# Kickliter_Trevor_Lab_9.net
KiCad netlist of a schematic drawn in EAGLE
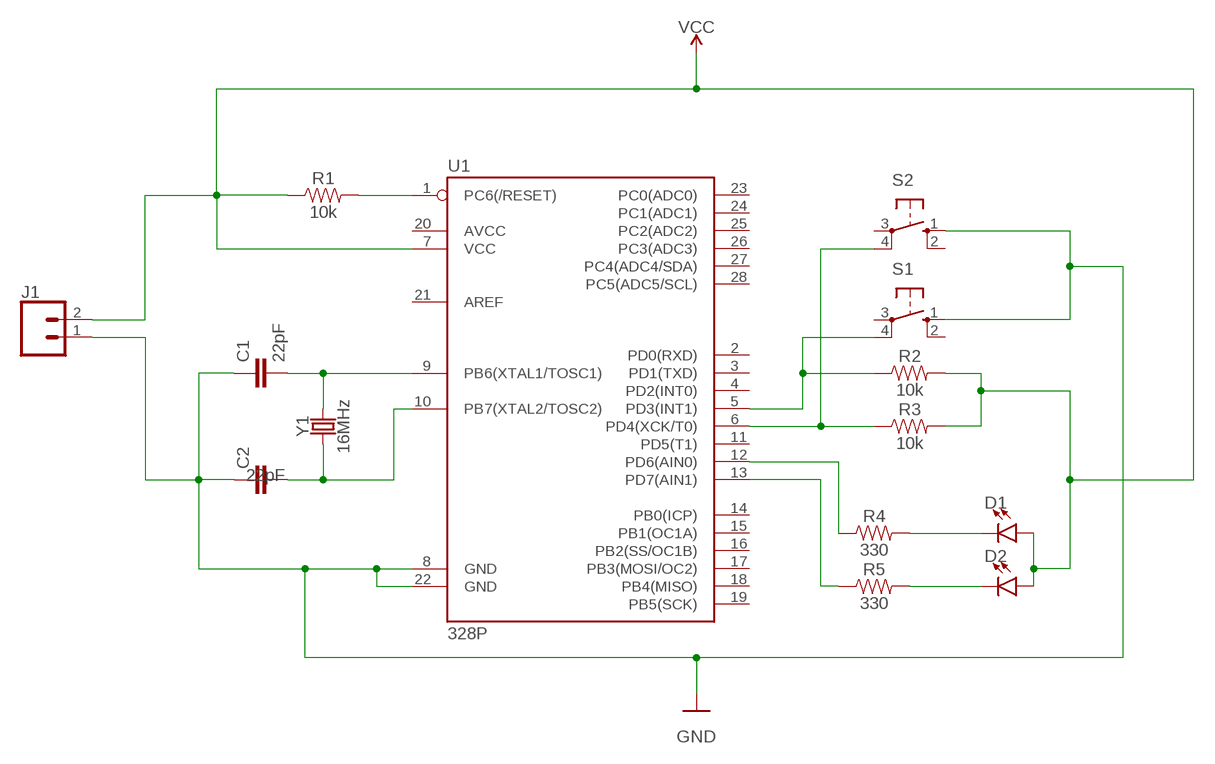
[diagram p0: schematic, sheet 1]

(export (version "E")
  (design (tool "Eeschema 10.0.6"))
  (components
    (comp (ref "C1")
      (value "22pF")
      (footprint "eagle-import:CAP-PTH-2.54")
      (libsource (lib "eagle-import") (part "22PF-PTH-2.54MM-200V-5%"))
    )
    (comp (ref "C2")
      (value "22pF")
      (footprint "eagle-import:CAP-PTH-2.54")
      (libsource (lib "eagle-import") (part "22PF-PTH-2.54MM-200V-5%"))
    )
    (comp (ref "D1")
      (value "LED-3MM-NO_SILK")
      (footprint "eagle-import:LED_3MM-NS")
      (libsource (lib "eagle-import") (part "LED-3MM-NO_SILK"))
    )
    (comp (ref "D2")
      (value "LED-3MM-NO_SILK")
      (footprint "eagle-import:LED_3MM-NS")
      (libsource (lib "eagle-import") (part "LED-3MM-NO_SILK"))
    )
    (comp (ref "J1")
      (value "CONN_02")
      (footprint "eagle-import:1X02")
      (libsource (lib "eagle-import") (part "CONN_02"))
    )
    (comp (ref "R1")
      (value "10k")
      (footprint "eagle-import:AXIAL-0.3")
      (libsource (lib "eagle-import") (part "10KOHM-HORIZ-1/4W-5%"))
    )
    (comp (ref "R2")
      (value "10k")
      (footprint "eagle-import:AXIAL-0.3")
      (libsource (lib "eagle-import") (part "10KOHM-HORIZ-1/4W-1%"))
    )
    (comp (ref "R3")
      (value "10k")
      (footprint "eagle-import:AXIAL-0.3")
      (libsource (lib "eagle-import") (part "10KOHM-HORIZ-1/4W-1%"))
    )
    (comp (ref "R4")
      (value "330")
      (footprint "eagle-import:AXIAL-0.3")
      (libsource (lib "eagle-import") (part "330OHM-HORIZ-1/10W-5%"))
    )
    (comp (ref "R5")
      (value "330")
      (footprint "eagle-import:AXIAL-0.3")
      (libsource (lib "eagle-import") (part "330OHM-HORIZ-1/10W-5%"))
    )
    (comp (ref "S1")
      (value "10-XX")
      (footprint "eagle-import:B3F-10XX")
      (fields (field (name "MPN") "B3F-1000"))
      (libsource (lib "eagle-import") (part "10-XX"))
    )
    (comp (ref "S2")
      (value "10-XX")
      (footprint "eagle-import:B3F-10XX")
      (fields (field (name "MPN") "B3F-1000"))
      (libsource (lib "eagle-import") (part "10-XX"))
    )
    (comp (ref "U1")
      (value "328P")
      (footprint "eagle-import:DIP28")
      (libsource (lib "eagle-import") (part "ATMEGA328P_PDIP"))
    )
    (comp (ref "Y1")
      (value "16MHz")
      (footprint "eagle-import:HC49US")
      (libsource (lib "eagle-import") (part "CRYSTAL-16MHZPTH-HC49US"))
    )
  )
  (nets
    (net (code "1") (name "GND") (class "Default")
      (node (ref "C1") (pin "1") (pinfunction "1_1") (pintype "passive"))
      (node (ref "C2") (pin "1") (pinfunction "1_1") (pintype "passive"))
      (node (ref "J1") (pin "1") (pinfunction "1_1") (pintype "passive"))
      (node (ref "S1") (pin "1") (pinfunction "S_1") (pintype "passive"))
      (node (ref "S2") (pin "1") (pinfunction "S_1") (pintype "passive"))
      (node (ref "U1") (pin "22") (pinfunction "GND_22") (pintype "bidirectional"))
      (node (ref "U1") (pin "8") (pinfunction "GND_8") (pintype "bidirectional"))
    )
    (net (code "2") (name "Net-(D1-C)") (class "Default")
      (node (ref "D1") (pin "K") (pinfunction "C_K") (pintype "passive"))
      (node (ref "R4") (pin "P$2") (pinfunction "2_P$2") (pintype "passive"))
    )
    (net (code "3") (name "Net-(D2-C)") (class "Default")
      (node (ref "D2") (pin "K") (pinfunction "C_K") (pintype "passive"))
      (node (ref "R5") (pin "P$2") (pinfunction "2_P$2") (pintype "passive"))
    )
    (net (code "4") (name "Net-(R1-2)") (class "Default")
      (node (ref "R1") (pin "P$2") (pinfunction "2_P$2") (pintype "passive"))
      (node (ref "U1") (pin "1") (pinfunction "PC6(/RESET)_1") (pintype "bidirectional"))
    )
    (net (code "5") (name "Net-(R2-1)") (class "Default")
      (node (ref "R2") (pin "P$1") (pinfunction "1_P$1") (pintype "passive"))
      (node (ref "S1") (pin "4") (pinfunction "P1_4") (pintype "passive"))
      (node (ref "U1") (pin "5") (pinfunction "PD3(INT1)_5") (pintype "bidirectional"))
    )
    (net (code "6") (name "Net-(R3-1)") (class "Default")
      (node (ref "R3") (pin "P$1") (pinfunction "1_P$1") (pintype "passive"))
      (node (ref "S2") (pin "4") (pinfunction "P1_4") (pintype "passive"))
      (node (ref "U1") (pin "6") (pinfunction "PD4(XCK/T0)_6") (pintype "bidirectional"))
    )
    (net (code "7") (name "Net-(R4-1)") (class "Default")
      (node (ref "R4") (pin "P$1") (pinfunction "1_P$1") (pintype "passive"))
      (node (ref "U1") (pin "12") (pinfunction "PD6(AIN0)_12") (pintype "bidirectional"))
    )
    (net (code "8") (name "Net-(R5-1)") (class "Default")
      (node (ref "R5") (pin "P$1") (pinfunction "1_P$1") (pintype "passive"))
      (node (ref "U1") (pin "13") (pinfunction "PD7(AIN1)_13") (pintype "bidirectional"))
    )
    (net (code "9") (name "Net-(U1-PB6(XTAL1{slash}TOSC1))") (class "Default")
      (node (ref "C1") (pin "2") (pinfunction "2_2") (pintype "passive"))
      (node (ref "U1") (pin "9") (pinfunction "PB6(XTAL1/TOSC1)_9") (pintype "bidirectional"))
      (node (ref "Y1") (pin "2") (pinfunction "2_2") (pintype "passive"))
    )
    (net (code "10") (name "Net-(U1-PB7(XTAL2{slash}TOSC2))") (class "Default")
      (node (ref "C2") (pin "2") (pinfunction "2_2") (pintype "passive"))
      (node (ref "U1") (pin "10") (pinfunction "PB7(XTAL2/TOSC2)_10") (pintype "bidirectional"))
      (node (ref "Y1") (pin "1") (pinfunction "1_1") (pintype "passive"))
    )
    (net (code "11") (name "VCC") (class "Default")
      (node (ref "D1") (pin "A") (pinfunction "A_A") (pintype "passive"))
      (node (ref "D2") (pin "A") (pinfunction "A_A") (pintype "passive"))
      (node (ref "J1") (pin "2") (pinfunction "2_2") (pintype "passive"))
      (node (ref "R1") (pin "P$1") (pinfunction "1_P$1") (pintype "passive"))
      (node (ref "R2") (pin "P$2") (pinfunction "2_P$2") (pintype "passive"))
      (node (ref "R3") (pin "P$2") (pinfunction "2_P$2") (pintype "passive"))
      (node (ref "U1") (pin "7") (pinfunction "VCC_7") (pintype "bidirectional"))
    )
    (net (code "12") (name "unconnected-(S1-P-Pad3)") (class "Default")
      (node (ref "S1") (pin "3") (pinfunction "P_3") (pintype "passive"))
    )
    (net (code "13") (name "unconnected-(S1-S1-Pad2)") (class "Default")
      (node (ref "S1") (pin "2") (pinfunction "S1_2") (pintype "passive"))
    )
    (net (code "14") (name "unconnected-(S2-P-Pad3)") (class "Default")
      (node (ref "S2") (pin "3") (pinfunction "P_3") (pintype "passive"))
    )
    (net (code "15") (name "unconnected-(S2-S1-Pad2)") (class "Default")
      (node (ref "S2") (pin "2") (pinfunction "S1_2") (pintype "passive"))
    )
    (net (code "16") (name "unconnected-(U1-AREF-Pad21)") (class "Default")
      (node (ref "U1") (pin "21") (pinfunction "AREF_21") (pintype "bidirectional"))
    )
    (net (code "17") (name "unconnected-(U1-AVCC-Pad20)") (class "Default")
      (node (ref "U1") (pin "20") (pinfunction "AVCC_20") (pintype "bidirectional"))
    )
    (net (code "18") (name "unconnected-(U1-PB0(ICP)-Pad14)") (class "Default")
      (node (ref "U1") (pin "14") (pinfunction "PB0(ICP)_14") (pintype "bidirectional"))
    )
    (net (code "19") (name "unconnected-(U1-PB1(OC1A)-Pad15)") (class "Default")
      (node (ref "U1") (pin "15") (pinfunction "PB1(OC1A)_15") (pintype "bidirectional"))
    )
    (net (code "20") (name "unconnected-(U1-PB2(SS{slash}OC1B)-Pad16)") (class "Default")
      (node (ref "U1") (pin "16") (pinfunction "PB2(SS/OC1B)_16") (pintype "bidirectional"))
    )
    (net (code "21") (name "unconnected-(U1-PB3(MOSI{slash}OC2)-Pad17)") (class "Default")
      (node (ref "U1") (pin "17") (pinfunction "PB3(MOSI/OC2)_17") (pintype "bidirectional"))
    )
    (net (code "22") (name "unconnected-(U1-PB4(MISO)-Pad18)") (class "Default")
      (node (ref "U1") (pin "18") (pinfunction "PB4(MISO)_18") (pintype "bidirectional"))
    )
    (net (code "23") (name "unconnected-(U1-PB5(SCK)-Pad19)") (class "Default")
      (node (ref "U1") (pin "19") (pinfunction "PB5(SCK)_19") (pintype "bidirectional"))
    )
    (net (code "24") (name "unconnected-(U1-PC0(ADC0)-Pad23)") (class "Default")
      (node (ref "U1") (pin "23") (pinfunction "PC0(ADC0)_23") (pintype "bidirectional"))
    )
    (net (code "25") (name "unconnected-(U1-PC1(ADC1)-Pad24)") (class "Default")
      (node (ref "U1") (pin "24") (pinfunction "PC1(ADC1)_24") (pintype "bidirectional"))
    )
    (net (code "26") (name "unconnected-(U1-PC2(ADC2)-Pad25)") (class "Default")
      (node (ref "U1") (pin "25") (pinfunction "PC2(ADC2)_25") (pintype "bidirectional"))
    )
    (net (code "27") (name "unconnected-(U1-PC3(ADC3)-Pad26)") (class "Default")
      (node (ref "U1") (pin "26") (pinfunction "PC3(ADC3)_26") (pintype "bidirectional"))
    )
    (net (code "28") (name "unconnected-(U1-PC4(ADC4{slash}SDA)-Pad27)") (class "Default")
      (node (ref "U1") (pin "27") (pinfunction "PC4(ADC4/SDA)_27") (pintype "bidirectional"))
    )
    (net (code "29") (name "unconnected-(U1-PC5(ADC5{slash}SCL)-Pad28)") (class "Default")
      (node (ref "U1") (pin "28") (pinfunction "PC5(ADC5/SCL)_28") (pintype "bidirectional"))
    )
    (net (code "30") (name "unconnected-(U1-PD0(RXD)-Pad2)") (class "Default")
      (node (ref "U1") (pin "2") (pinfunction "PD0(RXD)_2") (pintype "bidirectional"))
    )
    (net (code "31") (name "unconnected-(U1-PD1(TXD)-Pad3)") (class "Default")
      (node (ref "U1") (pin "3") (pinfunction "PD1(TXD)_3") (pintype "bidirectional"))
    )
    (net (code "32") (name "unconnected-(U1-PD2(INT0)-Pad4)") (class "Default")
      (node (ref "U1") (pin "4") (pinfunction "PD2(INT0)_4") (pintype "bidirectional"))
    )
    (net (code "33") (name "unconnected-(U1-PD5(T1)-Pad11)") (class "Default")
      (node (ref "U1") (pin "11") (pinfunction "PD5(T1)_11") (pintype "bidirectional"))
    )
  )
)
